# HDMI_Termination.net
KiCad netlist of a schematic drawn in Altium Designer
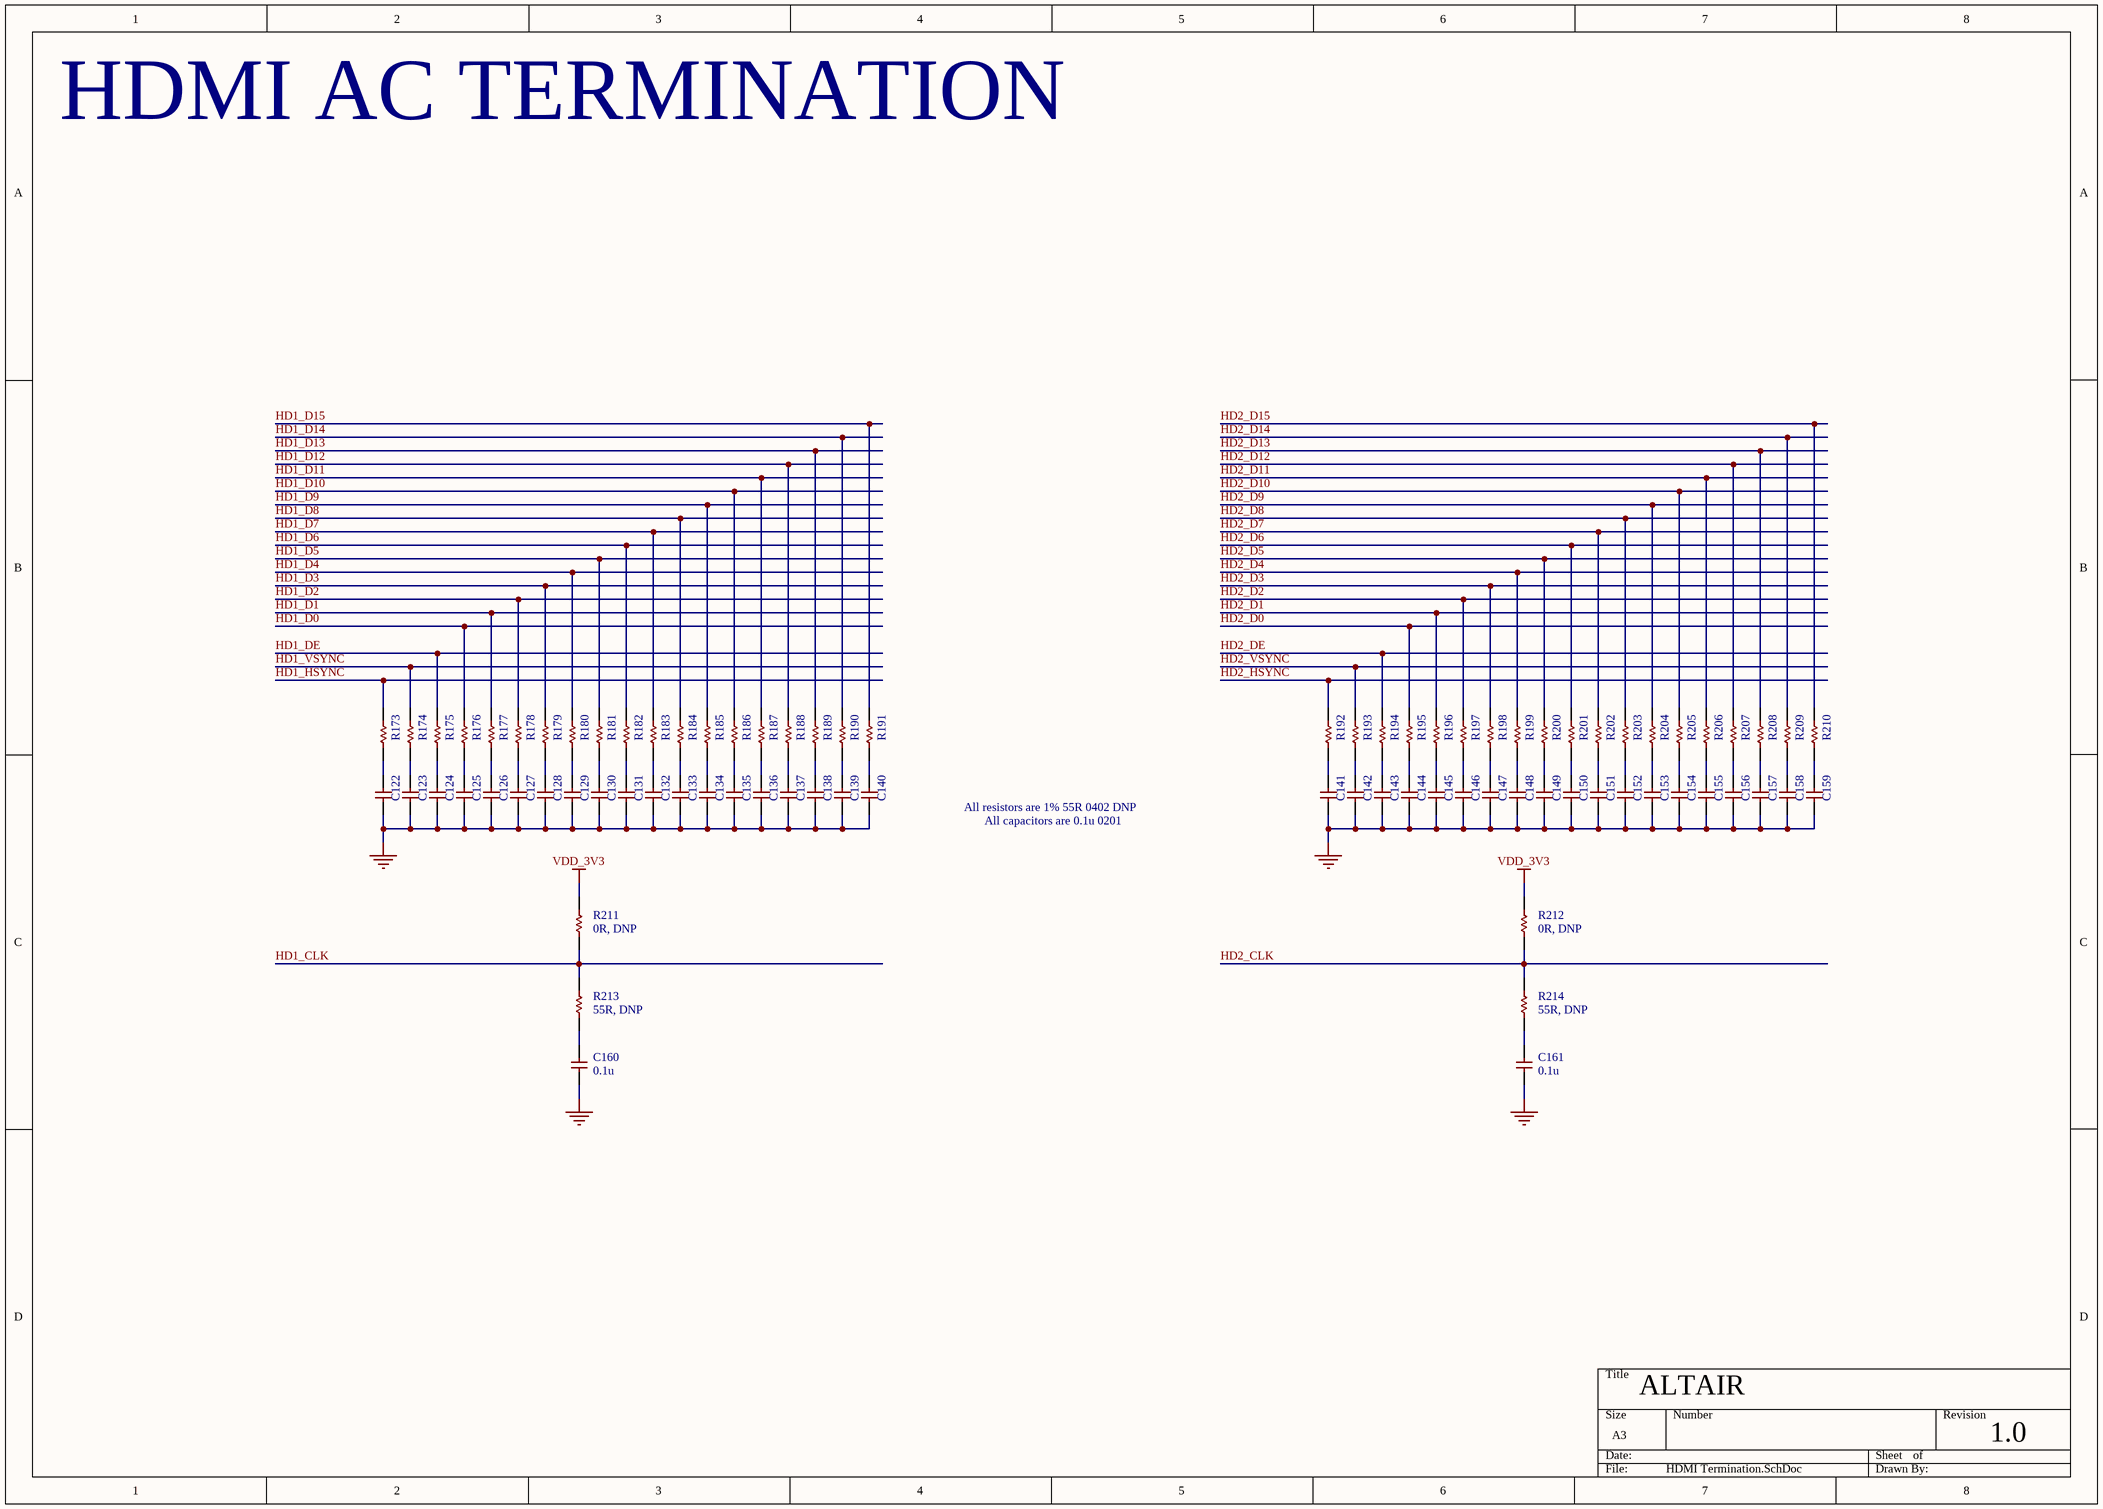
[diagram p0: HDMI Termination.SchDoc]

(export (version "E")
  (design (tool "Eeschema 10.0.6"))
  (components
    (comp (ref "C122")
      (value "0.1u")
      (footprint "CAP_0201")
      (description "Capacitor SMD 0201")
      (fields (field (name "PART NO") "CL03A104KP3NNNC") (field (name "JLCPCB PART #") "C49062"))
      (libsource (lib "personalGenericLib") (part "CAP_0201"))
    )
    (comp (ref "C123")
      (value "0.1u")
      (footprint "CAP_0201")
      (description "Capacitor SMD 0201")
      (fields (field (name "PART NO") "CL03A104KP3NNNC") (field (name "JLCPCB PART #") "C49062"))
      (libsource (lib "personalGenericLib") (part "CAP_0201"))
    )
    (comp (ref "C124")
      (value "0.1u")
      (footprint "CAP_0201")
      (description "Capacitor SMD 0201")
      (fields (field (name "PART NO") "CL03A104KP3NNNC") (field (name "JLCPCB PART #") "C49062"))
      (libsource (lib "personalGenericLib") (part "CAP_0201"))
    )
    (comp (ref "C125")
      (value "0.1u")
      (footprint "CAP_0201")
      (description "Capacitor SMD 0201")
      (fields (field (name "PART NO") "CL03A104KP3NNNC") (field (name "JLCPCB PART #") "C49062"))
      (libsource (lib "personalGenericLib") (part "CAP_0201"))
    )
    (comp (ref "C126")
      (value "0.1u")
      (footprint "CAP_0201")
      (description "Capacitor SMD 0201")
      (fields (field (name "PART NO") "CL03A104KP3NNNC") (field (name "JLCPCB PART #") "C49062"))
      (libsource (lib "personalGenericLib") (part "CAP_0201"))
    )
    (comp (ref "C127")
      (value "0.1u")
      (footprint "CAP_0201")
      (description "Capacitor SMD 0201")
      (fields (field (name "PART NO") "CL03A104KP3NNNC") (field (name "JLCPCB PART #") "C49062"))
      (libsource (lib "personalGenericLib") (part "CAP_0201"))
    )
    (comp (ref "C128")
      (value "0.1u")
      (footprint "CAP_0201")
      (description "Capacitor SMD 0201")
      (fields (field (name "PART NO") "CL03A104KP3NNNC") (field (name "JLCPCB PART #") "C49062"))
      (libsource (lib "personalGenericLib") (part "CAP_0201"))
    )
    (comp (ref "C129")
      (value "0.1u")
      (footprint "CAP_0201")
      (description "Capacitor SMD 0201")
      (fields (field (name "PART NO") "CL03A104KP3NNNC") (field (name "JLCPCB PART #") "C49062"))
      (libsource (lib "personalGenericLib") (part "CAP_0201"))
    )
    (comp (ref "C130")
      (value "0.1u")
      (footprint "CAP_0201")
      (description "Capacitor SMD 0201")
      (fields (field (name "PART NO") "CL03A104KP3NNNC") (field (name "JLCPCB PART #") "C49062"))
      (libsource (lib "personalGenericLib") (part "CAP_0201"))
    )
    (comp (ref "C131")
      (value "0.1u")
      (footprint "CAP_0201")
      (description "Capacitor SMD 0201")
      (fields (field (name "PART NO") "CL03A104KP3NNNC") (field (name "JLCPCB PART #") "C49062"))
      (libsource (lib "personalGenericLib") (part "CAP_0201"))
    )
    (comp (ref "C132")
      (value "0.1u")
      (footprint "CAP_0201")
      (description "Capacitor SMD 0201")
      (fields (field (name "PART NO") "CL03A104KP3NNNC") (field (name "JLCPCB PART #") "C49062"))
      (libsource (lib "personalGenericLib") (part "CAP_0201"))
    )
    (comp (ref "C133")
      (value "0.1u")
      (footprint "CAP_0201")
      (description "Capacitor SMD 0201")
      (fields (field (name "PART NO") "CL03A104KP3NNNC") (field (name "JLCPCB PART #") "C49062"))
      (libsource (lib "personalGenericLib") (part "CAP_0201"))
    )
    (comp (ref "C134")
      (value "0.1u")
      (footprint "CAP_0201")
      (description "Capacitor SMD 0201")
      (fields (field (name "PART NO") "CL03A104KP3NNNC") (field (name "JLCPCB PART #") "C49062"))
      (libsource (lib "personalGenericLib") (part "CAP_0201"))
    )
    (comp (ref "C135")
      (value "0.1u")
      (footprint "CAP_0201")
      (description "Capacitor SMD 0201")
      (fields (field (name "PART NO") "CL03A104KP3NNNC") (field (name "JLCPCB PART #") "C49062"))
      (libsource (lib "personalGenericLib") (part "CAP_0201"))
    )
    (comp (ref "C136")
      (value "0.1u")
      (footprint "CAP_0201")
      (description "Capacitor SMD 0201")
      (fields (field (name "PART NO") "CL03A104KP3NNNC") (field (name "JLCPCB PART #") "C49062"))
      (libsource (lib "personalGenericLib") (part "CAP_0201"))
    )
    (comp (ref "C137")
      (value "0.1u")
      (footprint "CAP_0201")
      (description "Capacitor SMD 0201")
      (fields (field (name "PART NO") "CL03A104KP3NNNC") (field (name "JLCPCB PART #") "C49062"))
      (libsource (lib "personalGenericLib") (part "CAP_0201"))
    )
    (comp (ref "C138")
      (value "0.1u")
      (footprint "CAP_0201")
      (description "Capacitor SMD 0201")
      (fields (field (name "PART NO") "CL03A104KP3NNNC") (field (name "JLCPCB PART #") "C49062"))
      (libsource (lib "personalGenericLib") (part "CAP_0201"))
    )
    (comp (ref "C139")
      (value "0.1u")
      (footprint "CAP_0201")
      (description "Capacitor SMD 0201")
      (fields (field (name "PART NO") "CL03A104KP3NNNC") (field (name "JLCPCB PART #") "C49062"))
      (libsource (lib "personalGenericLib") (part "CAP_0201"))
    )
    (comp (ref "C140")
      (value "0.1u")
      (footprint "CAP_0201")
      (description "Capacitor SMD 0201")
      (fields (field (name "PART NO") "CL03A104KP3NNNC") (field (name "JLCPCB PART #") "C49062"))
      (libsource (lib "personalGenericLib") (part "CAP_0201"))
    )
    (comp (ref "C141")
      (value "0.1u")
      (footprint "CAP_0201")
      (description "Capacitor SMD 0201")
      (fields (field (name "PART NO") "CL03A104KP3NNNC") (field (name "JLCPCB PART #") "C49062"))
      (libsource (lib "personalGenericLib") (part "CAP_0201"))
    )
    (comp (ref "C142")
      (value "0.1u")
      (footprint "CAP_0201")
      (description "Capacitor SMD 0201")
      (fields (field (name "PART NO") "CL03A104KP3NNNC") (field (name "JLCPCB PART #") "C49062"))
      (libsource (lib "personalGenericLib") (part "CAP_0201"))
    )
    (comp (ref "C143")
      (value "0.1u")
      (footprint "CAP_0201")
      (description "Capacitor SMD 0201")
      (fields (field (name "PART NO") "CL03A104KP3NNNC") (field (name "JLCPCB PART #") "C49062"))
      (libsource (lib "personalGenericLib") (part "CAP_0201"))
    )
    (comp (ref "C144")
      (value "0.1u")
      (footprint "CAP_0201")
      (description "Capacitor SMD 0201")
      (fields (field (name "PART NO") "CL03A104KP3NNNC") (field (name "JLCPCB PART #") "C49062"))
      (libsource (lib "personalGenericLib") (part "CAP_0201"))
    )
    (comp (ref "C145")
      (value "0.1u")
      (footprint "CAP_0201")
      (description "Capacitor SMD 0201")
      (fields (field (name "PART NO") "CL03A104KP3NNNC") (field (name "JLCPCB PART #") "C49062"))
      (libsource (lib "personalGenericLib") (part "CAP_0201"))
    )
    (comp (ref "C146")
      (value "0.1u")
      (footprint "CAP_0201")
      (description "Capacitor SMD 0201")
      (fields (field (name "PART NO") "CL03A104KP3NNNC") (field (name "JLCPCB PART #") "C49062"))
      (libsource (lib "personalGenericLib") (part "CAP_0201"))
    )
    (comp (ref "C147")
      (value "0.1u")
      (footprint "CAP_0201")
      (description "Capacitor SMD 0201")
      (fields (field (name "PART NO") "CL03A104KP3NNNC") (field (name "JLCPCB PART #") "C49062"))
      (libsource (lib "personalGenericLib") (part "CAP_0201"))
    )
    (comp (ref "C148")
      (value "0.1u")
      (footprint "CAP_0201")
      (description "Capacitor SMD 0201")
      (fields (field (name "PART NO") "CL03A104KP3NNNC") (field (name "JLCPCB PART #") "C49062"))
      (libsource (lib "personalGenericLib") (part "CAP_0201"))
    )
    (comp (ref "C149")
      (value "0.1u")
      (footprint "CAP_0201")
      (description "Capacitor SMD 0201")
      (fields (field (name "PART NO") "CL03A104KP3NNNC") (field (name "JLCPCB PART #") "C49062"))
      (libsource (lib "personalGenericLib") (part "CAP_0201"))
    )
    (comp (ref "C150")
      (value "0.1u")
      (footprint "CAP_0201")
      (description "Capacitor SMD 0201")
      (fields (field (name "PART NO") "CL03A104KP3NNNC") (field (name "JLCPCB PART #") "C49062"))
      (libsource (lib "personalGenericLib") (part "CAP_0201"))
    )
    (comp (ref "C151")
      (value "0.1u")
      (footprint "CAP_0201")
      (description "Capacitor SMD 0201")
      (fields (field (name "PART NO") "CL03A104KP3NNNC") (field (name "JLCPCB PART #") "C49062"))
      (libsource (lib "personalGenericLib") (part "CAP_0201"))
    )
    (comp (ref "C152")
      (value "0.1u")
      (footprint "CAP_0201")
      (description "Capacitor SMD 0201")
      (fields (field (name "PART NO") "CL03A104KP3NNNC") (field (name "JLCPCB PART #") "C49062"))
      (libsource (lib "personalGenericLib") (part "CAP_0201"))
    )
    (comp (ref "C153")
      (value "0.1u")
      (footprint "CAP_0201")
      (description "Capacitor SMD 0201")
      (fields (field (name "PART NO") "CL03A104KP3NNNC") (field (name "JLCPCB PART #") "C49062"))
      (libsource (lib "personalGenericLib") (part "CAP_0201"))
    )
    (comp (ref "C154")
      (value "0.1u")
      (footprint "CAP_0201")
      (description "Capacitor SMD 0201")
      (fields (field (name "PART NO") "CL03A104KP3NNNC") (field (name "JLCPCB PART #") "C49062"))
      (libsource (lib "personalGenericLib") (part "CAP_0201"))
    )
    (comp (ref "C155")
      (value "0.1u")
      (footprint "CAP_0201")
      (description "Capacitor SMD 0201")
      (fields (field (name "PART NO") "CL03A104KP3NNNC") (field (name "JLCPCB PART #") "C49062"))
      (libsource (lib "personalGenericLib") (part "CAP_0201"))
    )
    (comp (ref "C156")
      (value "0.1u")
      (footprint "CAP_0201")
      (description "Capacitor SMD 0201")
      (fields (field (name "PART NO") "CL03A104KP3NNNC") (field (name "JLCPCB PART #") "C49062"))
      (libsource (lib "personalGenericLib") (part "CAP_0201"))
    )
    (comp (ref "C157")
      (value "0.1u")
      (footprint "CAP_0201")
      (description "Capacitor SMD 0201")
      (fields (field (name "PART NO") "CL03A104KP3NNNC") (field (name "JLCPCB PART #") "C49062"))
      (libsource (lib "personalGenericLib") (part "CAP_0201"))
    )
    (comp (ref "C158")
      (value "0.1u")
      (footprint "CAP_0201")
      (description "Capacitor SMD 0201")
      (fields (field (name "PART NO") "CL03A104KP3NNNC") (field (name "JLCPCB PART #") "C49062"))
      (libsource (lib "personalGenericLib") (part "CAP_0201"))
    )
    (comp (ref "C159")
      (value "0.1u")
      (footprint "CAP_0201")
      (description "Capacitor SMD 0201")
      (fields (field (name "PART NO") "CL03A104KP3NNNC") (field (name "JLCPCB PART #") "C49062"))
      (libsource (lib "personalGenericLib") (part "CAP_0201"))
    )
    (comp (ref "C160")
      (value "0.1u")
      (footprint "CAP_0201")
      (description "Capacitor SMD 0201")
      (fields (field (name "PART NO") "CL03A104KP3NNNC") (field (name "JLCPCB PART #") "C49062"))
      (libsource (lib "personalGenericLib") (part "CAP_0201"))
    )
    (comp (ref "C161")
      (value "0.1u")
      (footprint "CAP_0201")
      (description "Capacitor SMD 0201")
      (fields (field (name "PART NO") "CL03A104KP3NNNC") (field (name "JLCPCB PART #") "C49062"))
      (libsource (lib "personalGenericLib") (part "CAP_0201"))
    )
    (comp (ref "R173")
      (value "0R, DNP")
      (footprint "RES_0402")
      (description "Resistor SMD 0402")
      (fields (field (name "PART NO") "RC0402JR-070RL") (field (name "JLCPCB PART #") "C60485"))
      (libsource (lib "personalGenericLib") (part "RES_0402"))
    )
    (comp (ref "R174")
      (value "0R, DNP")
      (footprint "RES_0402")
      (description "Resistor SMD 0402")
      (fields (field (name "PART NO") "RC0402JR-070RL") (field (name "JLCPCB PART #") "C60485"))
      (libsource (lib "personalGenericLib") (part "RES_0402"))
    )
    (comp (ref "R175")
      (value "0R, DNP")
      (footprint "RES_0402")
      (description "Resistor SMD 0402")
      (fields (field (name "PART NO") "RC0402JR-070RL") (field (name "JLCPCB PART #") "C60485"))
      (libsource (lib "personalGenericLib") (part "RES_0402"))
    )
    (comp (ref "R176")
      (value "0R, DNP")
      (footprint "RES_0402")
      (description "Resistor SMD 0402")
      (fields (field (name "PART NO") "RC0402JR-070RL") (field (name "JLCPCB PART #") "C60485"))
      (libsource (lib "personalGenericLib") (part "RES_0402"))
    )
    (comp (ref "R177")
      (value "0R, DNP")
      (footprint "RES_0402")
      (description "Resistor SMD 0402")
      (fields (field (name "PART NO") "RC0402JR-070RL") (field (name "JLCPCB PART #") "C60485"))
      (libsource (lib "personalGenericLib") (part "RES_0402"))
    )
    (comp (ref "R178")
      (value "0R, DNP")
      (footprint "RES_0402")
      (description "Resistor SMD 0402")
      (fields (field (name "PART NO") "RC0402JR-070RL") (field (name "JLCPCB PART #") "C60485"))
      (libsource (lib "personalGenericLib") (part "RES_0402"))
    )
    (comp (ref "R179")
      (value "0R, DNP")
      (footprint "RES_0402")
      (description "Resistor SMD 0402")
      (fields (field (name "PART NO") "RC0402JR-070RL") (field (name "JLCPCB PART #") "C60485"))
      (libsource (lib "personalGenericLib") (part "RES_0402"))
    )
    (comp (ref "R180")
      (value "0R, DNP")
      (footprint "RES_0402")
      (description "Resistor SMD 0402")
      (fields (field (name "PART NO") "RC0402JR-070RL") (field (name "JLCPCB PART #") "C60485"))
      (libsource (lib "personalGenericLib") (part "RES_0402"))
    )
    (comp (ref "R181")
      (value "0R, DNP")
      (footprint "RES_0402")
      (description "Resistor SMD 0402")
      (fields (field (name "PART NO") "RC0402JR-070RL") (field (name "JLCPCB PART #") "C60485"))
      (libsource (lib "personalGenericLib") (part "RES_0402"))
    )
    (comp (ref "R182")
      (value "0R, DNP")
      (footprint "RES_0402")
      (description "Resistor SMD 0402")
      (fields (field (name "PART NO") "RC0402JR-070RL") (field (name "JLCPCB PART #") "C60485"))
      (libsource (lib "personalGenericLib") (part "RES_0402"))
    )
    (comp (ref "R183")
      (value "0R, DNP")
      (footprint "RES_0402")
      (description "Resistor SMD 0402")
      (fields (field (name "PART NO") "RC0402JR-070RL") (field (name "JLCPCB PART #") "C60485"))
      (libsource (lib "personalGenericLib") (part "RES_0402"))
    )
    (comp (ref "R184")
      (value "0R, DNP")
      (footprint "RES_0402")
      (description "Resistor SMD 0402")
      (fields (field (name "PART NO") "RC0402JR-070RL") (field (name "JLCPCB PART #") "C60485"))
      (libsource (lib "personalGenericLib") (part "RES_0402"))
    )
    (comp (ref "R185")
      (value "0R, DNP")
      (footprint "RES_0402")
      (description "Resistor SMD 0402")
      (fields (field (name "PART NO") "RC0402JR-070RL") (field (name "JLCPCB PART #") "C60485"))
      (libsource (lib "personalGenericLib") (part "RES_0402"))
    )
    (comp (ref "R186")
      (value "0R, DNP")
      (footprint "RES_0402")
      (description "Resistor SMD 0402")
      (fields (field (name "PART NO") "RC0402JR-070RL") (field (name "JLCPCB PART #") "C60485"))
      (libsource (lib "personalGenericLib") (part "RES_0402"))
    )
    (comp (ref "R187")
      (value "0R, DNP")
      (footprint "RES_0402")
      (description "Resistor SMD 0402")
      (fields (field (name "PART NO") "RC0402JR-070RL") (field (name "JLCPCB PART #") "C60485"))
      (libsource (lib "personalGenericLib") (part "RES_0402"))
    )
    (comp (ref "R188")
      (value "0R, DNP")
      (footprint "RES_0402")
      (description "Resistor SMD 0402")
      (fields (field (name "PART NO") "RC0402JR-070RL") (field (name "JLCPCB PART #") "C60485"))
      (libsource (lib "personalGenericLib") (part "RES_0402"))
    )
    (comp (ref "R189")
      (value "0R, DNP")
      (footprint "RES_0402")
      (description "Resistor SMD 0402")
      (fields (field (name "PART NO") "RC0402JR-070RL") (field (name "JLCPCB PART #") "C60485"))
      (libsource (lib "personalGenericLib") (part "RES_0402"))
    )
    (comp (ref "R190")
      (value "0R, DNP")
      (footprint "RES_0402")
      (description "Resistor SMD 0402")
      (fields (field (name "PART NO") "RC0402JR-070RL") (field (name "JLCPCB PART #") "C60485"))
      (libsource (lib "personalGenericLib") (part "RES_0402"))
    )
    (comp (ref "R191")
      (value "0R, DNP")
      (footprint "RES_0402")
      (description "Resistor SMD 0402")
      (fields (field (name "PART NO") "RC0402JR-070RL") (field (name "JLCPCB PART #") "C60485"))
      (libsource (lib "personalGenericLib") (part "RES_0402"))
    )
    (comp (ref "R192")
      (value "0R, DNP")
      (footprint "RES_0402")
      (description "Resistor SMD 0402")
      (fields (field (name "PART NO") "RC0402JR-070RL") (field (name "JLCPCB PART #") "C60485"))
      (libsource (lib "personalGenericLib") (part "RES_0402"))
    )
    (comp (ref "R193")
      (value "0R, DNP")
      (footprint "RES_0402")
      (description "Resistor SMD 0402")
      (fields (field (name "PART NO") "RC0402JR-070RL") (field (name "JLCPCB PART #") "C60485"))
      (libsource (lib "personalGenericLib") (part "RES_0402"))
    )
    (comp (ref "R194")
      (value "0R, DNP")
      (footprint "RES_0402")
      (description "Resistor SMD 0402")
      (fields (field (name "PART NO") "RC0402JR-070RL") (field (name "JLCPCB PART #") "C60485"))
      (libsource (lib "personalGenericLib") (part "RES_0402"))
    )
    (comp (ref "R195")
      (value "0R, DNP")
      (footprint "RES_0402")
      (description "Resistor SMD 0402")
      (fields (field (name "PART NO") "RC0402JR-070RL") (field (name "JLCPCB PART #") "C60485"))
      (libsource (lib "personalGenericLib") (part "RES_0402"))
    )
    (comp (ref "R196")
      (value "0R, DNP")
      (footprint "RES_0402")
      (description "Resistor SMD 0402")
      (fields (field (name "PART NO") "RC0402JR-070RL") (field (name "JLCPCB PART #") "C60485"))
      (libsource (lib "personalGenericLib") (part "RES_0402"))
    )
    (comp (ref "R197")
      (value "0R, DNP")
      (footprint "RES_0402")
      (description "Resistor SMD 0402")
      (fields (field (name "PART NO") "RC0402JR-070RL") (field (name "JLCPCB PART #") "C60485"))
      (libsource (lib "personalGenericLib") (part "RES_0402"))
    )
    (comp (ref "R198")
      (value "0R, DNP")
      (footprint "RES_0402")
      (description "Resistor SMD 0402")
      (fields (field (name "PART NO") "RC0402JR-070RL") (field (name "JLCPCB PART #") "C60485"))
      (libsource (lib "personalGenericLib") (part "RES_0402"))
    )
    (comp (ref "R199")
      (value "0R, DNP")
      (footprint "RES_0402")
      (description "Resistor SMD 0402")
      (fields (field (name "PART NO") "RC0402JR-070RL") (field (name "JLCPCB PART #") "C60485"))
      (libsource (lib "personalGenericLib") (part "RES_0402"))
    )
    (comp (ref "R200")
      (value "0R, DNP")
      (footprint "RES_0402")
      (description "Resistor SMD 0402")
      (fields (field (name "PART NO") "RC0402JR-070RL") (field (name "JLCPCB PART #") "C60485"))
      (libsource (lib "personalGenericLib") (part "RES_0402"))
    )
    (comp (ref "R201")
      (value "0R, DNP")
      (footprint "RES_0402")
      (description "Resistor SMD 0402")
      (fields (field (name "PART NO") "RC0402JR-070RL") (field (name "JLCPCB PART #") "C60485"))
      (libsource (lib "personalGenericLib") (part "RES_0402"))
    )
    (comp (ref "R202")
      (value "0R, DNP")
      (footprint "RES_0402")
      (description "Resistor SMD 0402")
      (fields (field (name "PART NO") "RC0402JR-070RL") (field (name "JLCPCB PART #") "C60485"))
      (libsource (lib "personalGenericLib") (part "RES_0402"))
    )
    (comp (ref "R203")
      (value "0R, DNP")
      (footprint "RES_0402")
      (description "Resistor SMD 0402")
      (fields (field (name "PART NO") "RC0402JR-070RL") (field (name "JLCPCB PART #") "C60485"))
      (libsource (lib "personalGenericLib") (part "RES_0402"))
    )
    (comp (ref "R204")
      (value "0R, DNP")
      (footprint "RES_0402")
      (description "Resistor SMD 0402")
      (fields (field (name "PART NO") "RC0402JR-070RL") (field (name "JLCPCB PART #") "C60485"))
      (libsource (lib "personalGenericLib") (part "RES_0402"))
    )
    (comp (ref "R205")
      (value "0R, DNP")
      (footprint "RES_0402")
      (description "Resistor SMD 0402")
      (fields (field (name "PART NO") "RC0402JR-070RL") (field (name "JLCPCB PART #") "C60485"))
      (libsource (lib "personalGenericLib") (part "RES_0402"))
    )
    (comp (ref "R206")
      (value "0R, DNP")
      (footprint "RES_0402")
      (description "Resistor SMD 0402")
      (fields (field (name "PART NO") "RC0402JR-070RL") (field (name "JLCPCB PART #") "C60485"))
      (libsource (lib "personalGenericLib") (part "RES_0402"))
    )
    (comp (ref "R207")
      (value "0R, DNP")
      (footprint "RES_0402")
      (description "Resistor SMD 0402")
      (fields (field (name "PART NO") "RC0402JR-070RL") (field (name "JLCPCB PART #") "C60485"))
      (libsource (lib "personalGenericLib") (part "RES_0402"))
    )
    (comp (ref "R208")
      (value "0R, DNP")
      (footprint "RES_0402")
      (description "Resistor SMD 0402")
      (fields (field (name "PART NO") "RC0402JR-070RL") (field (name "JLCPCB PART #") "C60485"))
      (libsource (lib "personalGenericLib") (part "RES_0402"))
    )
    (comp (ref "R209")
      (value "0R, DNP")
      (footprint "RES_0402")
      (description "Resistor SMD 0402")
      (fields (field (name "PART NO") "RC0402JR-070RL") (field (name "JLCPCB PART #") "C60485"))
      (libsource (lib "personalGenericLib") (part "RES_0402"))
    )
    (comp (ref "R210")
      (value "0R, DNP")
      (footprint "RES_0402")
      (description "Resistor SMD 0402")
      (fields (field (name "PART NO") "RC0402JR-070RL") (field (name "JLCPCB PART #") "C60485"))
      (libsource (lib "personalGenericLib") (part "RES_0402"))
    )
    (comp (ref "R211")
      (value "0R, DNP")
      (footprint "RES_0402")
      (description "Resistor SMD 0402")
      (fields (field (name "PART NO") "RC0402JR-070RL") (field (name "JLCPCB PART #") "C60485"))
      (libsource (lib "personalGenericLib") (part "RES_0402"))
    )
    (comp (ref "R212")
      (value "0R, DNP")
      (footprint "RES_0402")
      (description "Resistor SMD 0402")
      (fields (field (name "PART NO") "RC0402JR-070RL") (field (name "JLCPCB PART #") "C60485"))
      (libsource (lib "personalGenericLib") (part "RES_0402"))
    )
    (comp (ref "R213")
      (value "55R, DNP")
      (footprint "RES_0402")
      (description "Resistor SMD 0402")
      (libsource (lib "personalGenericLib") (part "RES_0402"))
    )
    (comp (ref "R214")
      (value "55R, DNP")
      (footprint "RES_0402")
      (description "Resistor SMD 0402")
      (libsource (lib "personalGenericLib") (part "RES_0402"))
    )
  )
  (nets
    (net (code "1") (name "/HD1_CLK") (class "Default")
      (node (ref "R211") (pin "1") (pinfunction "1_1") (pintype "passive"))
      (node (ref "R213") (pin "2") (pinfunction "2_2") (pintype "passive"))
    )
    (net (code "2") (name "/HD1_D0") (class "Default")
      (node (ref "R176") (pin "2") (pinfunction "2_2") (pintype "passive"))
    )
    (net (code "3") (name "/HD1_D1") (class "Default")
      (node (ref "R177") (pin "2") (pinfunction "2_2") (pintype "passive"))
    )
    (net (code "4") (name "/HD1_D2") (class "Default")
      (node (ref "R178") (pin "2") (pinfunction "2_2") (pintype "passive"))
    )
    (net (code "5") (name "/HD1_D3") (class "Default")
      (node (ref "R179") (pin "2") (pinfunction "2_2") (pintype "passive"))
    )
    (net (code "6") (name "/HD1_D4") (class "Default")
      (node (ref "R180") (pin "2") (pinfunction "2_2") (pintype "passive"))
    )
    (net (code "7") (name "/HD1_D5") (class "Default")
      (node (ref "R181") (pin "2") (pinfunction "2_2") (pintype "passive"))
    )
    (net (code "8") (name "/HD1_D6") (class "Default")
      (node (ref "R182") (pin "2") (pinfunction "2_2") (pintype "passive"))
    )
    (net (code "9") (name "/HD1_D7") (class "Default")
      (node (ref "R183") (pin "2") (pinfunction "2_2") (pintype "passive"))
    )
    (net (code "10") (name "/HD1_D8") (class "Default")
      (node (ref "R184") (pin "2") (pinfunction "2_2") (pintype "passive"))
    )
    (net (code "11") (name "/HD1_D9") (class "Default")
      (node (ref "R185") (pin "2") (pinfunction "2_2") (pintype "passive"))
    )
    (net (code "12") (name "/HD1_D10") (class "Default")
      (node (ref "R186") (pin "2") (pinfunction "2_2") (pintype "passive"))
    )
    (net (code "13") (name "/HD1_D11") (class "Default")
      (node (ref "R187") (pin "2") (pinfunction "2_2") (pintype "passive"))
    )
    (net (code "14") (name "/HD1_D12") (class "Default")
      (node (ref "R188") (pin "2") (pinfunction "2_2") (pintype "passive"))
    )
    (net (code "15") (name "/HD1_D13") (class "Default")
      (node (ref "R189") (pin "2") (pinfunction "2_2") (pintype "passive"))
    )
    (net (code "16") (name "/HD1_D14") (class "Default")
      (node (ref "R190") (pin "2") (pinfunction "2_2") (pintype "passive"))
    )
    (net (code "17") (name "/HD1_D15") (class "Default")
      (node (ref "R191") (pin "2") (pinfunction "2_2") (pintype "passive"))
    )
    (net (code "18") (name "/HD1_DE") (class "Default")
      (node (ref "R175") (pin "2") (pinfunction "2_2") (pintype "passive"))
    )
    (net (code "19") (name "/HD1_HSYNC") (class "Default")
      (node (ref "R173") (pin "2") (pinfunction "2_2") (pintype "passive"))
    )
    (net (code "20") (name "/HD1_VSYNC") (class "Default")
      (node (ref "R174") (pin "2") (pinfunction "2_2") (pintype "passive"))
    )
    (net (code "21") (name "/HD2_CLK") (class "Default")
      (node (ref "R212") (pin "1") (pinfunction "1_1") (pintype "passive"))
      (node (ref "R214") (pin "2") (pinfunction "2_2") (pintype "passive"))
    )
    (net (code "22") (name "/HD2_D0") (class "Default")
      (node (ref "R195") (pin "2") (pinfunction "2_2") (pintype "passive"))
    )
    (net (code "23") (name "/HD2_D1") (class "Default")
      (node (ref "R196") (pin "2") (pinfunction "2_2") (pintype "passive"))
    )
    (net (code "24") (name "/HD2_D2") (class "Default")
      (node (ref "R197") (pin "2") (pinfunction "2_2") (pintype "passive"))
    )
    (net (code "25") (name "/HD2_D3") (class "Default")
      (node (ref "R198") (pin "2") (pinfunction "2_2") (pintype "passive"))
    )
    (net (code "26") (name "/HD2_D4") (class "Default")
      (node (ref "R199") (pin "2") (pinfunction "2_2") (pintype "passive"))
    )
    (net (code "27") (name "/HD2_D5") (class "Default")
      (node (ref "R200") (pin "2") (pinfunction "2_2") (pintype "passive"))
    )
    (net (code "28") (name "/HD2_D6") (class "Default")
      (node (ref "R201") (pin "2") (pinfunction "2_2") (pintype "passive"))
    )
    (net (code "29") (name "/HD2_D7") (class "Default")
      (node (ref "R202") (pin "2") (pinfunction "2_2") (pintype "passive"))
    )
    (net (code "30") (name "/HD2_D8") (class "Default")
      (node (ref "R203") (pin "2") (pinfunction "2_2") (pintype "passive"))
    )
    (net (code "31") (name "/HD2_D9") (class "Default")
      (node (ref "R204") (pin "2") (pinfunction "2_2") (pintype "passive"))
    )
    (net (code "32") (name "/HD2_D10") (class "Default")
      (node (ref "R205") (pin "2") (pinfunction "2_2") (pintype "passive"))
    )
    (net (code "33") (name "/HD2_D11") (class "Default")
      (node (ref "R206") (pin "2") (pinfunction "2_2") (pintype "passive"))
    )
    (net (code "34") (name "/HD2_D12") (class "Default")
      (node (ref "R207") (pin "2") (pinfunction "2_2") (pintype "passive"))
    )
    (net (code "35") (name "/HD2_D13") (class "Default")
      (node (ref "R208") (pin "2") (pinfunction "2_2") (pintype "passive"))
    )
    (net (code "36") (name "/HD2_D14") (class "Default")
      (node (ref "R209") (pin "2") (pinfunction "2_2") (pintype "passive"))
    )
    (net (code "37") (name "/HD2_D15") (class "Default")
      (node (ref "R210") (pin "2") (pinfunction "2_2") (pintype "passive"))
    )
    (net (code "38") (name "/HD2_DE") (class "Default")
      (node (ref "R194") (pin "2") (pinfunction "2_2") (pintype "passive"))
    )
    (net (code "39") (name "/HD2_HSYNC") (class "Default")
      (node (ref "R192") (pin "2") (pinfunction "2_2") (pintype "passive"))
    )
    (net (code "40") (name "/HD2_VSYNC") (class "Default")
      (node (ref "R193") (pin "2") (pinfunction "2_2") (pintype "passive"))
    )
    (net (code "41") (name "GND") (class "Default")
      (node (ref "C122") (pin "1") (pinfunction "1_1") (pintype "passive"))
      (node (ref "C123") (pin "1") (pinfunction "1_1") (pintype "passive"))
      (node (ref "C124") (pin "1") (pinfunction "1_1") (pintype "passive"))
      (node (ref "C125") (pin "1") (pinfunction "1_1") (pintype "passive"))
      (node (ref "C126") (pin "1") (pinfunction "1_1") (pintype "passive"))
      (node (ref "C127") (pin "1") (pinfunction "1_1") (pintype "passive"))
      (node (ref "C128") (pin "1") (pinfunction "1_1") (pintype "passive"))
      (node (ref "C129") (pin "1") (pinfunction "1_1") (pintype "passive"))
      (node (ref "C130") (pin "1") (pinfunction "1_1") (pintype "passive"))
      (node (ref "C131") (pin "1") (pinfunction "1_1") (pintype "passive"))
      (node (ref "C132") (pin "1") (pinfunction "1_1") (pintype "passive"))
      (node (ref "C133") (pin "1") (pinfunction "1_1") (pintype "passive"))
      (node (ref "C134") (pin "1") (pinfunction "1_1") (pintype "passive"))
      (node (ref "C135") (pin "1") (pinfunction "1_1") (pintype "passive"))
      (node (ref "C136") (pin "1") (pinfunction "1_1") (pintype "passive"))
      (node (ref "C137") (pin "1") (pinfunction "1_1") (pintype "passive"))
      (node (ref "C138") (pin "1") (pinfunction "1_1") (pintype "passive"))
      (node (ref "C139") (pin "1") (pinfunction "1_1") (pintype "passive"))
      (node (ref "C140") (pin "1") (pinfunction "1_1") (pintype "passive"))
      (node (ref "C141") (pin "1") (pinfunction "1_1") (pintype "passive"))
      (node (ref "C142") (pin "1") (pinfunction "1_1") (pintype "passive"))
      (node (ref "C143") (pin "1") (pinfunction "1_1") (pintype "passive"))
      (node (ref "C144") (pin "1") (pinfunction "1_1") (pintype "passive"))
      (node (ref "C145") (pin "1") (pinfunction "1_1") (pintype "passive"))
      (node (ref "C146") (pin "1") (pinfunction "1_1") (pintype "passive"))
      (node (ref "C147") (pin "1") (pinfunction "1_1") (pintype "passive"))
      (node (ref "C148") (pin "1") (pinfunction "1_1") (pintype "passive"))
      (node (ref "C149") (pin "1") (pinfunction "1_1") (pintype "passive"))
      (node (ref "C150") (pin "1") (pinfunction "1_1") (pintype "passive"))
      (node (ref "C151") (pin "1") (pinfunction "1_1") (pintype "passive"))
      (node (ref "C152") (pin "1") (pinfunction "1_1") (pintype "passive"))
      (node (ref "C153") (pin "1") (pinfunction "1_1") (pintype "passive"))
      (node (ref "C154") (pin "1") (pinfunction "1_1") (pintype "passive"))
      (node (ref "C155") (pin "1") (pinfunction "1_1") (pintype "passive"))
      (node (ref "C156") (pin "1") (pinfunction "1_1") (pintype "passive"))
      (node (ref "C157") (pin "1") (pinfunction "1_1") (pintype "passive"))
      (node (ref "C158") (pin "1") (pinfunction "1_1") (pintype "passive"))
      (node (ref "C159") (pin "1") (pinfunction "1_1") (pintype "passive"))
      (node (ref "C160") (pin "1") (pinfunction "1_1") (pintype "passive"))
      (node (ref "C161") (pin "1") (pinfunction "1_1") (pintype "passive"))
    )
    (net (code "42") (name "Net-(C122-Pad2)") (class "Default")
      (node (ref "C122") (pin "2") (pinfunction "2_2") (pintype "passive"))
      (node (ref "R173") (pin "1") (pinfunction "1_1") (pintype "passive"))
    )
    (net (code "43") (name "Net-(C123-Pad2)") (class "Default")
      (node (ref "C123") (pin "2") (pinfunction "2_2") (pintype "passive"))
      (node (ref "R174") (pin "1") (pinfunction "1_1") (pintype "passive"))
    )
    (net (code "44") (name "Net-(C124-Pad2)") (class "Default")
      (node (ref "C124") (pin "2") (pinfunction "2_2") (pintype "passive"))
      (node (ref "R175") (pin "1") (pinfunction "1_1") (pintype "passive"))
    )
    (net (code "45") (name "Net-(C125-Pad2)") (class "Default")
      (node (ref "C125") (pin "2") (pinfunction "2_2") (pintype "passive"))
      (node (ref "R176") (pin "1") (pinfunction "1_1") (pintype "passive"))
    )
    (net (code "46") (name "Net-(C126-Pad2)") (class "Default")
      (node (ref "C126") (pin "2") (pinfunction "2_2") (pintype "passive"))
      (node (ref "R177") (pin "1") (pinfunction "1_1") (pintype "passive"))
    )
    (net (code "47") (name "Net-(C127-Pad2)") (class "Default")
      (node (ref "C127") (pin "2") (pinfunction "2_2") (pintype "passive"))
      (node (ref "R178") (pin "1") (pinfunction "1_1") (pintype "passive"))
    )
    (net (code "48") (name "Net-(C128-Pad2)") (class "Default")
      (node (ref "C128") (pin "2") (pinfunction "2_2") (pintype "passive"))
      (node (ref "R179") (pin "1") (pinfunction "1_1") (pintype "passive"))
    )
    (net (code "49") (name "Net-(C129-Pad2)") (class "Default")
      (node (ref "C129") (pin "2") (pinfunction "2_2") (pintype "passive"))
      (node (ref "R180") (pin "1") (pinfunction "1_1") (pintype "passive"))
    )
    (net (code "50") (name "Net-(C130-Pad2)") (class "Default")
      (node (ref "C130") (pin "2") (pinfunction "2_2") (pintype "passive"))
      (node (ref "R181") (pin "1") (pinfunction "1_1") (pintype "passive"))
    )
    (net (code "51") (name "Net-(C131-Pad2)") (class "Default")
      (node (ref "C131") (pin "2") (pinfunction "2_2") (pintype "passive"))
      (node (ref "R182") (pin "1") (pinfunction "1_1") (pintype "passive"))
    )
    (net (code "52") (name "Net-(C132-Pad2)") (class "Default")
      (node (ref "C132") (pin "2") (pinfunction "2_2") (pintype "passive"))
      (node (ref "R183") (pin "1") (pinfunction "1_1") (pintype "passive"))
    )
    (net (code "53") (name "Net-(C133-Pad2)") (class "Default")
      (node (ref "C133") (pin "2") (pinfunction "2_2") (pintype "passive"))
      (node (ref "R184") (pin "1") (pinfunction "1_1") (pintype "passive"))
    )
    (net (code "54") (name "Net-(C134-Pad2)") (class "Default")
      (node (ref "C134") (pin "2") (pinfunction "2_2") (pintype "passive"))
      (node (ref "R185") (pin "1") (pinfunction "1_1") (pintype "passive"))
    )
    (net (code "55") (name "Net-(C135-Pad2)") (class "Default")
      (node (ref "C135") (pin "2") (pinfunction "2_2") (pintype "passive"))
      (node (ref "R186") (pin "1") (pinfunction "1_1") (pintype "passive"))
    )
    (net (code "56") (name "Net-(C136-Pad2)") (class "Default")
      (node (ref "C136") (pin "2") (pinfunction "2_2") (pintype "passive"))
      (node (ref "R187") (pin "1") (pinfunction "1_1") (pintype "passive"))
    )
    (net (code "57") (name "Net-(C137-Pad2)") (class "Default")
      (node (ref "C137") (pin "2") (pinfunction "2_2") (pintype "passive"))
      (node (ref "R188") (pin "1") (pinfunction "1_1") (pintype "passive"))
    )
    (net (code "58") (name "Net-(C138-Pad2)") (class "Default")
      (node (ref "C138") (pin "2") (pinfunction "2_2") (pintype "passive"))
      (node (ref "R189") (pin "1") (pinfunction "1_1") (pintype "passive"))
    )
    (net (code "59") (name "Net-(C139-Pad2)") (class "Default")
      (node (ref "C139") (pin "2") (pinfunction "2_2") (pintype "passive"))
      (node (ref "R190") (pin "1") (pinfunction "1_1") (pintype "passive"))
    )
    (net (code "60") (name "Net-(C140-Pad2)") (class "Default")
      (node (ref "C140") (pin "2") (pinfunction "2_2") (pintype "passive"))
      (node (ref "R191") (pin "1") (pinfunction "1_1") (pintype "passive"))
    )
    (net (code "61") (name "Net-(C141-Pad2)") (class "Default")
      (node (ref "C141") (pin "2") (pinfunction "2_2") (pintype "passive"))
      (node (ref "R192") (pin "1") (pinfunction "1_1") (pintype "passive"))
    )
    (net (code "62") (name "Net-(C142-Pad2)") (class "Default")
      (node (ref "C142") (pin "2") (pinfunction "2_2") (pintype "passive"))
      (node (ref "R193") (pin "1") (pinfunction "1_1") (pintype "passive"))
    )
    (net (code "63") (name "Net-(C143-Pad2)") (class "Default")
      (node (ref "C143") (pin "2") (pinfunction "2_2") (pintype "passive"))
      (node (ref "R194") (pin "1") (pinfunction "1_1") (pintype "passive"))
    )
    (net (code "64") (name "Net-(C144-Pad2)") (class "Default")
      (node (ref "C144") (pin "2") (pinfunction "2_2") (pintype "passive"))
      (node (ref "R195") (pin "1") (pinfunction "1_1") (pintype "passive"))
    )
    (net (code "65") (name "Net-(C145-Pad2)") (class "Default")
      (node (ref "C145") (pin "2") (pinfunction "2_2") (pintype "passive"))
      (node (ref "R196") (pin "1") (pinfunction "1_1") (pintype "passive"))
    )
    (net (code "66") (name "Net-(C146-Pad2)") (class "Default")
      (node (ref "C146") (pin "2") (pinfunction "2_2") (pintype "passive"))
      (node (ref "R197") (pin "1") (pinfunction "1_1") (pintype "passive"))
    )
    (net (code "67") (name "Net-(C147-Pad2)") (class "Default")
      (node (ref "C147") (pin "2") (pinfunction "2_2") (pintype "passive"))
      (node (ref "R198") (pin "1") (pinfunction "1_1") (pintype "passive"))
    )
    (net (code "68") (name "Net-(C148-Pad2)") (class "Default")
      (node (ref "C148") (pin "2") (pinfunction "2_2") (pintype "passive"))
      (node (ref "R199") (pin "1") (pinfunction "1_1") (pintype "passive"))
    )
    (net (code "69") (name "Net-(C149-Pad2)") (class "Default")
      (node (ref "C149") (pin "2") (pinfunction "2_2") (pintype "passive"))
      (node (ref "R200") (pin "1") (pinfunction "1_1") (pintype "passive"))
    )
    (net (code "70") (name "Net-(C150-Pad2)") (class "Default")
      (node (ref "C150") (pin "2") (pinfunction "2_2") (pintype "passive"))
      (node (ref "R201") (pin "1") (pinfunction "1_1") (pintype "passive"))
    )
    (net (code "71") (name "Net-(C151-Pad2)") (class "Default")
      (node (ref "C151") (pin "2") (pinfunction "2_2") (pintype "passive"))
      (node (ref "R202") (pin "1") (pinfunction "1_1") (pintype "passive"))
    )
    (net (code "72") (name "Net-(C152-Pad2)") (class "Default")
      (node (ref "C152") (pin "2") (pinfunction "2_2") (pintype "passive"))
      (node (ref "R203") (pin "1") (pinfunction "1_1") (pintype "passive"))
    )
    (net (code "73") (name "Net-(C153-Pad2)") (class "Default")
      (node (ref "C153") (pin "2") (pinfunction "2_2") (pintype "passive"))
      (node (ref "R204") (pin "1") (pinfunction "1_1") (pintype "passive"))
    )
    (net (code "74") (name "Net-(C154-Pad2)") (class "Default")
      (node (ref "C154") (pin "2") (pinfunction "2_2") (pintype "passive"))
      (node (ref "R205") (pin "1") (pinfunction "1_1") (pintype "passive"))
    )
    (net (code "75") (name "Net-(C155-Pad2)") (class "Default")
      (node (ref "C155") (pin "2") (pinfunction "2_2") (pintype "passive"))
      (node (ref "R206") (pin "1") (pinfunction "1_1") (pintype "passive"))
    )
    (net (code "76") (name "Net-(C156-Pad2)") (class "Default")
      (node (ref "C156") (pin "2") (pinfunction "2_2") (pintype "passive"))
      (node (ref "R207") (pin "1") (pinfunction "1_1") (pintype "passive"))
    )
    (net (code "77") (name "Net-(C157-Pad2)") (class "Default")
      (node (ref "C157") (pin "2") (pinfunction "2_2") (pintype "passive"))
      (node (ref "R208") (pin "1") (pinfunction "1_1") (pintype "passive"))
    )
    (net (code "78") (name "Net-(C158-Pad2)") (class "Default")
      (node (ref "C158") (pin "2") (pinfunction "2_2") (pintype "passive"))
      (node (ref "R209") (pin "1") (pinfunction "1_1") (pintype "passive"))
    )
    (net (code "79") (name "Net-(C159-Pad2)") (class "Default")
      (node (ref "C159") (pin "2") (pinfunction "2_2") (pintype "passive"))
      (node (ref "R210") (pin "1") (pinfunction "1_1") (pintype "passive"))
    )
    (net (code "80") (name "Net-(C160-Pad2)") (class "Default")
      (node (ref "C160") (pin "2") (pinfunction "2_2") (pintype "passive"))
      (node (ref "R213") (pin "1") (pinfunction "1_1") (pintype "passive"))
    )
    (net (code "81") (name "Net-(C161-Pad2)") (class "Default")
      (node (ref "C161") (pin "2") (pinfunction "2_2") (pintype "passive"))
      (node (ref "R214") (pin "1") (pinfunction "1_1") (pintype "passive"))
    )
    (net (code "82") (name "VDD_3V3") (class "Default")
      (node (ref "R211") (pin "2") (pinfunction "2_2") (pintype "passive"))
      (node (ref "R212") (pin "2") (pinfunction "2_2") (pintype "passive"))
    )
  )
)
